# control_bat.net
KiCad netlist of a schematic drawn in EAGLE
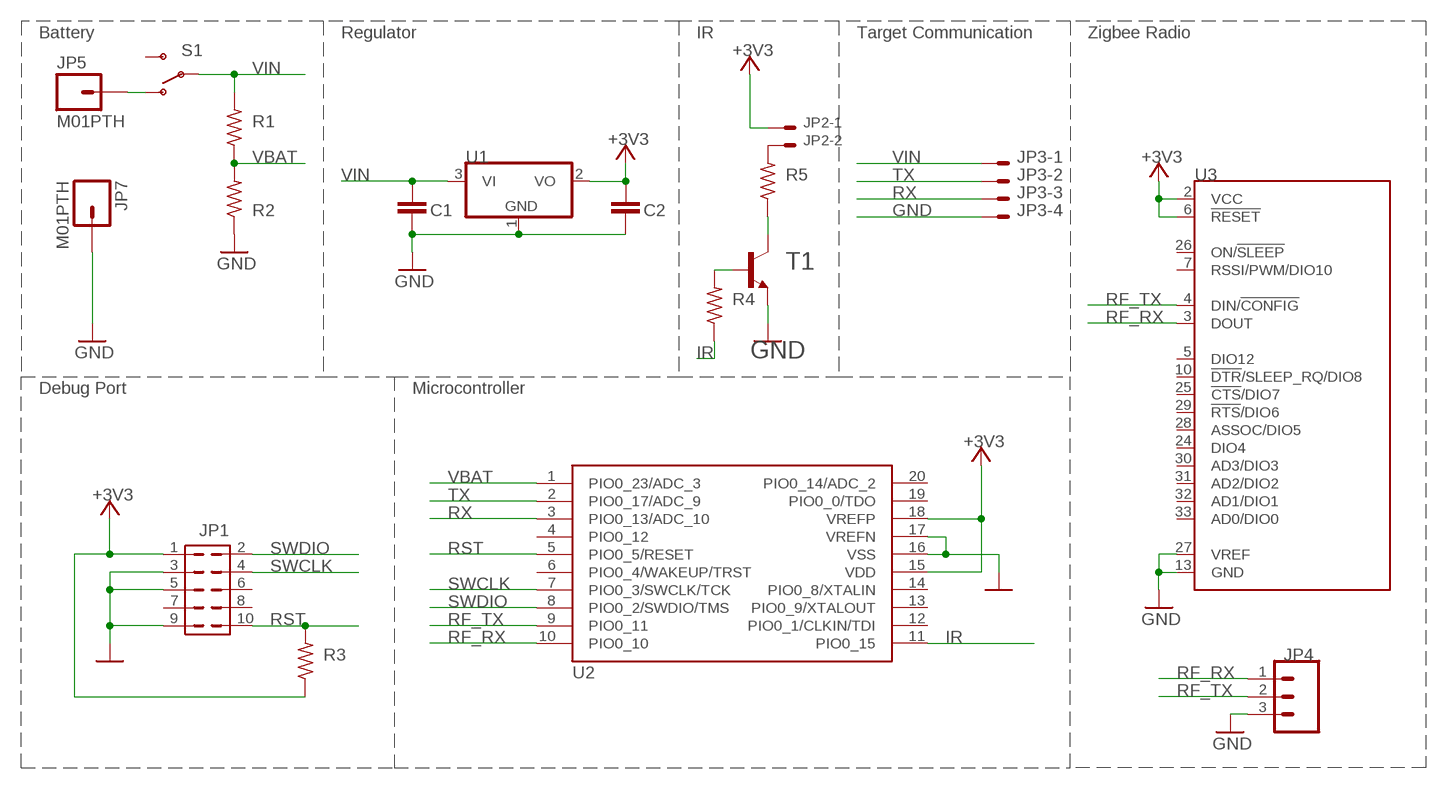
[diagram p0: schematic, sheet 1]

(export (version "E")
  (design (tool "Eeschema 10.0.6"))
  (components
    (comp (ref "C1")
      (value "C1608X5R1C106M080AB")
      (footprint "eagle-import:0603-CAP")
      (libsource (lib "eagle-import") (part "CAP0603-CAP"))
    )
    (comp (ref "C2")
      (value "C1608X5R1C106M080AB")
      (footprint "eagle-import:0603-CAP")
      (libsource (lib "eagle-import") (part "CAP0603-CAP"))
    )
    (comp (ref "JP1")
      (value "FTSH-105-01-L")
      (footprint "eagle-import:FTSH-105-01-XXX-DV-K")
      (libsource (lib "eagle-import") (part "FTSH-105"))
    )
    (comp (ref "JP2")
      (value "798-DF132P125V20")
      (footprint "eagle-import:53398-02")
      (libsource (lib "eagle-import") (part "53?-02398"))
    )
    (comp (ref "JP3")
      (value "798-DF134P125V20")
      (footprint "eagle-import:53398-04")
      (libsource (lib "eagle-import") (part "53?-04398"))
    )
    (comp (ref "JP4")
      (value "M03PTH")
      (footprint "eagle-import:1X03")
      (libsource (lib "eagle-import") (part "M03PTH"))
    )
    (comp (ref "JP5")
      (value "M01PTH")
      (footprint "eagle-import:1X01")
      (libsource (lib "eagle-import") (part "M01PTH"))
    )
    (comp (ref "JP7")
      (value "M01PTH")
      (footprint "eagle-import:1X01")
      (libsource (lib "eagle-import") (part "M01PTH"))
    )
    (comp (ref "R1")
      (value "71-CRCW0603-10K-E3")
      (footprint "eagle-import:R0603")
      (libsource (lib "eagle-import") (part "R-US_R0603"))
    )
    (comp (ref "R2")
      (value "71-CRCW0603-10K-E3")
      (footprint "eagle-import:R0603")
      (libsource (lib "eagle-import") (part "R-US_R0603"))
    )
    (comp (ref "R3")
      (value "71-CRCW0603-10K-E3")
      (footprint "eagle-import:R0603")
      (libsource (lib "eagle-import") (part "R-US_R0603"))
    )
    (comp (ref "R4")
      (value "71-CRCW0603220RFKEB")
      (footprint "eagle-import:R0603")
      (libsource (lib "eagle-import") (part "R-US_R0603"))
    )
    (comp (ref "R5")
      (value "71-CRCW0603-5.6-E3")
      (footprint "eagle-import:R0603")
      (libsource (lib "eagle-import") (part "R-US_R0603"))
    )
    (comp (ref "S1")
      (value "612-EG1270")
      (footprint "eagle-import:EG1270")
      (libsource (lib "eagle-import") (part "SWITCH-SPST"))
    )
    (comp (ref "T1")
      (value "PMBT4401,215")
      (footprint "eagle-import:SOT23-BEC")
      (libsource (lib "eagle-import") (part "-NPN-SOT23-BECMMBT4401LT1"))
    )
    (comp (ref "U1")
      (value "579-MCP1703T-3002ECB")
      (footprint "eagle-import:SOT23")
      (libsource (lib "eagle-import") (part "MCP1703CB"))
    )
    (comp (ref "U2")
      (value "771-LPC824M201JDH20J")
      (footprint "eagle-import:TSSOP20")
      (libsource (lib "eagle-import") (part "LPC824"))
    )
    (comp (ref "U3")
      (value "888-XB24CZ7PIS-004")
      (footprint "eagle-import:XBEE-SMT")
      (libsource (lib "eagle-import") (part "XBEE-SMT"))
    )
  )
  (nets
    (net (code "1") (name "+3V3") (class "Default")
      (node (ref "C2") (pin "1") (pinfunction "1_1") (pintype "passive"))
      (node (ref "JP1") (pin "1") (pinfunction "1_1") (pintype "passive"))
      (node (ref "JP2") (pin "1") (pinfunction "S_1") (pintype "passive"))
      (node (ref "R3") (pin "1") (pinfunction "1_1") (pintype "passive"))
      (node (ref "U1") (pin "2") (pinfunction "VO_2") (pintype "passive"))
      (node (ref "U2") (pin "15") (pinfunction "VDD_15") (pintype "bidirectional"))
      (node (ref "U2") (pin "18") (pinfunction "VREFP_18") (pintype "bidirectional"))
      (node (ref "U3") (pin "2") (pinfunction "VCC_2") (pintype "power_in"))
      (node (ref "U3") (pin "6") (pinfunction "~{RESET}_6") (pintype "input"))
    )
    (net (code "2") (name "/IR") (class "Default")
      (node (ref "R4") (pin "1") (pinfunction "1_1") (pintype "passive"))
      (node (ref "U2") (pin "11") (pinfunction "PIO0_15_11") (pintype "bidirectional"))
    )
    (net (code "3") (name "/RF_RX") (class "Default")
      (node (ref "JP4") (pin "1") (pinfunction "1_1") (pintype "passive"))
      (node (ref "U2") (pin "10") (pinfunction "PIO0_10_10") (pintype "bidirectional"))
      (node (ref "U3") (pin "3") (pinfunction "DOUT_3") (pintype "output"))
    )
    (net (code "4") (name "/RF_TX") (class "Default")
      (node (ref "JP4") (pin "2") (pinfunction "2_2") (pintype "passive"))
      (node (ref "U2") (pin "9") (pinfunction "PIO0_11_9") (pintype "bidirectional"))
      (node (ref "U3") (pin "4") (pinfunction "DIN/~{CONFIG}_4") (pintype "input"))
    )
    (net (code "5") (name "/RST") (class "Default")
      (node (ref "JP1") (pin "10") (pinfunction "10_10") (pintype "passive"))
      (node (ref "R3") (pin "2") (pinfunction "2_2") (pintype "passive"))
      (node (ref "U2") (pin "5") (pinfunction "PIO0_5/RESET_5") (pintype "bidirectional"))
    )
    (net (code "6") (name "/RX") (class "Default")
      (node (ref "JP3") (pin "3") (pinfunction "S_3") (pintype "passive"))
      (node (ref "U2") (pin "3") (pinfunction "PIO0_13/ADC_10_3") (pintype "bidirectional"))
    )
    (net (code "7") (name "/SWCLK") (class "Default")
      (node (ref "JP1") (pin "4") (pinfunction "4_4") (pintype "passive"))
      (node (ref "U2") (pin "7") (pinfunction "PIO0_3/SWCLK/TCK_7") (pintype "bidirectional"))
    )
    (net (code "8") (name "/SWDIO") (class "Default")
      (node (ref "JP1") (pin "2") (pinfunction "2_2") (pintype "passive"))
      (node (ref "U2") (pin "8") (pinfunction "PIO0_2/SWDIO/TMS_8") (pintype "bidirectional"))
    )
    (net (code "9") (name "/TX") (class "Default")
      (node (ref "JP3") (pin "2") (pinfunction "S_2") (pintype "passive"))
      (node (ref "U2") (pin "2") (pinfunction "PIO0_17/ADC_9_2") (pintype "bidirectional"))
    )
    (net (code "10") (name "/VBAT") (class "Default")
      (node (ref "R1") (pin "1") (pinfunction "1_1") (pintype "passive"))
      (node (ref "R2") (pin "2") (pinfunction "2_2") (pintype "passive"))
      (node (ref "U2") (pin "1") (pinfunction "PIO0_23/ADC_3_1") (pintype "bidirectional"))
    )
    (net (code "11") (name "/VIN") (class "Default")
      (node (ref "C1") (pin "1") (pinfunction "1_1") (pintype "passive"))
      (node (ref "JP3") (pin "1") (pinfunction "S_1") (pintype "passive"))
      (node (ref "R1") (pin "2") (pinfunction "2_2") (pintype "passive"))
      (node (ref "S1") (pin "P$2") (pinfunction "P_P$2") (pintype "passive"))
      (node (ref "U1") (pin "3") (pinfunction "VI_3") (pintype "input"))
    )
    (net (code "12") (name "GND") (class "Default")
      (node (ref "C1") (pin "2") (pinfunction "2_2") (pintype "passive"))
      (node (ref "C2") (pin "2") (pinfunction "2_2") (pintype "passive"))
      (node (ref "JP1") (pin "3") (pinfunction "3_3") (pintype "passive"))
      (node (ref "JP1") (pin "5") (pinfunction "5_5") (pintype "passive"))
      (node (ref "JP1") (pin "9") (pinfunction "9_9") (pintype "passive"))
      (node (ref "JP3") (pin "4") (pinfunction "S_4") (pintype "passive"))
      (node (ref "JP4") (pin "3") (pinfunction "3_3") (pintype "passive"))
      (node (ref "JP7") (pin "1") (pinfunction "1_1") (pintype "passive"))
      (node (ref "R2") (pin "1") (pinfunction "1_1") (pintype "passive"))
      (node (ref "T1") (pin "E") (pinfunction "E_E") (pintype "passive"))
      (node (ref "U1") (pin "1") (pinfunction "GND_1") (pintype "passive"))
      (node (ref "U2") (pin "16") (pinfunction "VSS_16") (pintype "bidirectional"))
      (node (ref "U2") (pin "17") (pinfunction "VREFN_17") (pintype "bidirectional"))
      (node (ref "U3") (pin "13") (pinfunction "GND_13") (pintype "power_in"))
      (node (ref "U3") (pin "27") (pinfunction "VREF_27") (pintype "input"))
    )
    (net (code "13") (name "Net-(JP2B-S)") (class "Default")
      (node (ref "JP2") (pin "2") (pinfunction "S_2") (pintype "passive"))
      (node (ref "R5") (pin "2") (pinfunction "2_2") (pintype "passive"))
    )
    (net (code "14") (name "Net-(R4-Pad2)") (class "Default")
      (node (ref "R4") (pin "2") (pinfunction "2_2") (pintype "passive"))
      (node (ref "T1") (pin "B") (pinfunction "B_B") (pintype "passive"))
    )
    (net (code "15") (name "Net-(R5-Pad1)") (class "Default")
      (node (ref "R5") (pin "1") (pinfunction "1_1") (pintype "passive"))
      (node (ref "T1") (pin "C") (pinfunction "C_C") (pintype "passive"))
    )
    (net (code "16") (name "Net-(S1-O)") (class "Default")
      (node (ref "JP5") (pin "1") (pinfunction "1_1") (pintype "passive"))
      (node (ref "S1") (pin "P$1") (pinfunction "O_P$1") (pintype "passive"))
    )
    (net (code "17") (name "unconnected-(JP1-Pad6)") (class "Default")
      (node (ref "JP1") (pin "6") (pinfunction "6_6") (pintype "passive"))
    )
    (net (code "18") (name "unconnected-(JP1-Pad7)") (class "Default")
      (node (ref "JP1") (pin "7") (pinfunction "7_7") (pintype "passive"))
    )
    (net (code "19") (name "unconnected-(JP1-Pad8)") (class "Default")
      (node (ref "JP1") (pin "8") (pinfunction "8_8") (pintype "passive"))
    )
    (net (code "20") (name "unconnected-(S1-S-PadP$3)") (class "Default")
      (node (ref "S1") (pin "P$3") (pinfunction "S_P$3") (pintype "passive"))
    )
    (net (code "21") (name "unconnected-(U2-PIO0_0{slash}TDO-Pad19)") (class "Default")
      (node (ref "U2") (pin "19") (pinfunction "PIO0_0/TDO_19") (pintype "bidirectional"))
    )
    (net (code "22") (name "unconnected-(U2-PIO0_1{slash}CLKIN{slash}TDI-Pad12)") (class "Default")
      (node (ref "U2") (pin "12") (pinfunction "PIO0_1/CLKIN/TDI_12") (pintype "bidirectional"))
    )
    (net (code "23") (name "unconnected-(U2-PIO0_4{slash}WAKEUP{slash}TRST-Pad6)") (class "Default")
      (node (ref "U2") (pin "6") (pinfunction "PIO0_4/WAKEUP/TRST_6") (pintype "bidirectional"))
    )
    (net (code "24") (name "unconnected-(U2-PIO0_8{slash}XTALIN-Pad14)") (class "Default")
      (node (ref "U2") (pin "14") (pinfunction "PIO0_8/XTALIN_14") (pintype "bidirectional"))
    )
    (net (code "25") (name "unconnected-(U2-PIO0_9{slash}XTALOUT-Pad13)") (class "Default")
      (node (ref "U2") (pin "13") (pinfunction "PIO0_9/XTALOUT_13") (pintype "bidirectional"))
    )
    (net (code "26") (name "unconnected-(U2-PIO0_12-Pad4)") (class "Default")
      (node (ref "U2") (pin "4") (pinfunction "PIO0_12_4") (pintype "bidirectional"))
    )
    (net (code "27") (name "unconnected-(U2-PIO0_14{slash}ADC_2-Pad20)") (class "Default")
      (node (ref "U2") (pin "20") (pinfunction "PIO0_14/ADC_2_20") (pintype "bidirectional"))
    )
    (net (code "28") (name "unconnected-(U3-AD0{slash}DIO0-Pad33)") (class "Default")
      (node (ref "U3") (pin "33") (pinfunction "AD0/DIO0_33") (pintype "bidirectional"))
    )
    (net (code "29") (name "unconnected-(U3-AD1{slash}DIO1-Pad32)") (class "Default")
      (node (ref "U3") (pin "32") (pinfunction "AD1/DIO1_32") (pintype "bidirectional"))
    )
    (net (code "30") (name "unconnected-(U3-AD2{slash}DIO2-Pad31)") (class "Default")
      (node (ref "U3") (pin "31") (pinfunction "AD2/DIO2_31") (pintype "bidirectional"))
    )
    (net (code "31") (name "unconnected-(U3-AD3{slash}DIO3-Pad30)") (class "Default")
      (node (ref "U3") (pin "30") (pinfunction "AD3/DIO3_30") (pintype "bidirectional"))
    )
    (net (code "32") (name "unconnected-(U3-ASSOC{slash}DIO5-Pad28)") (class "Default")
      (node (ref "U3") (pin "28") (pinfunction "ASSOC/DIO5_28") (pintype "bidirectional"))
    )
    (net (code "33") (name "unconnected-(U3-DIO4-Pad24)") (class "Default")
      (node (ref "U3") (pin "24") (pinfunction "DIO4_24") (pintype "bidirectional"))
    )
    (net (code "34") (name "unconnected-(U3-DIO12-Pad5)") (class "Default")
      (node (ref "U3") (pin "5") (pinfunction "DIO12_5") (pintype "bidirectional"))
    )
    (net (code "35") (name "unconnected-(U3-ON{slash}~{SLEEP}-Pad26)") (class "Default")
      (node (ref "U3") (pin "26") (pinfunction "ON/~{SLEEP}_26") (pintype "output"))
    )
    (net (code "36") (name "unconnected-(U3-RSSI{slash}PWM{slash}DIO10-Pad7)") (class "Default")
      (node (ref "U3") (pin "7") (pinfunction "RSSI/PWM/DIO10_7") (pintype "output"))
    )
    (net (code "37") (name "unconnected-(U3-~{CTS}{slash}DIO7-Pad25)") (class "Default")
      (node (ref "U3") (pin "25") (pinfunction "~{CTS}/DIO7_25") (pintype "bidirectional"))
    )
    (net (code "38") (name "unconnected-(U3-~{DTR}{slash}SLEEP_RQ{slash}DIO8-Pad10)") (class "Default")
      (node (ref "U3") (pin "10") (pinfunction "~{DTR}/SLEEP_RQ/DIO8_10") (pintype "bidirectional"))
    )
    (net (code "39") (name "unconnected-(U3-~{RTS}{slash}DIO6-Pad29)") (class "Default")
      (node (ref "U3") (pin "29") (pinfunction "~{RTS}/DIO6_29") (pintype "bidirectional"))
    )
  )
)
